# LM5161_Buck_Converter.net
KiCad netlist of a schematic drawn in Altium Designer
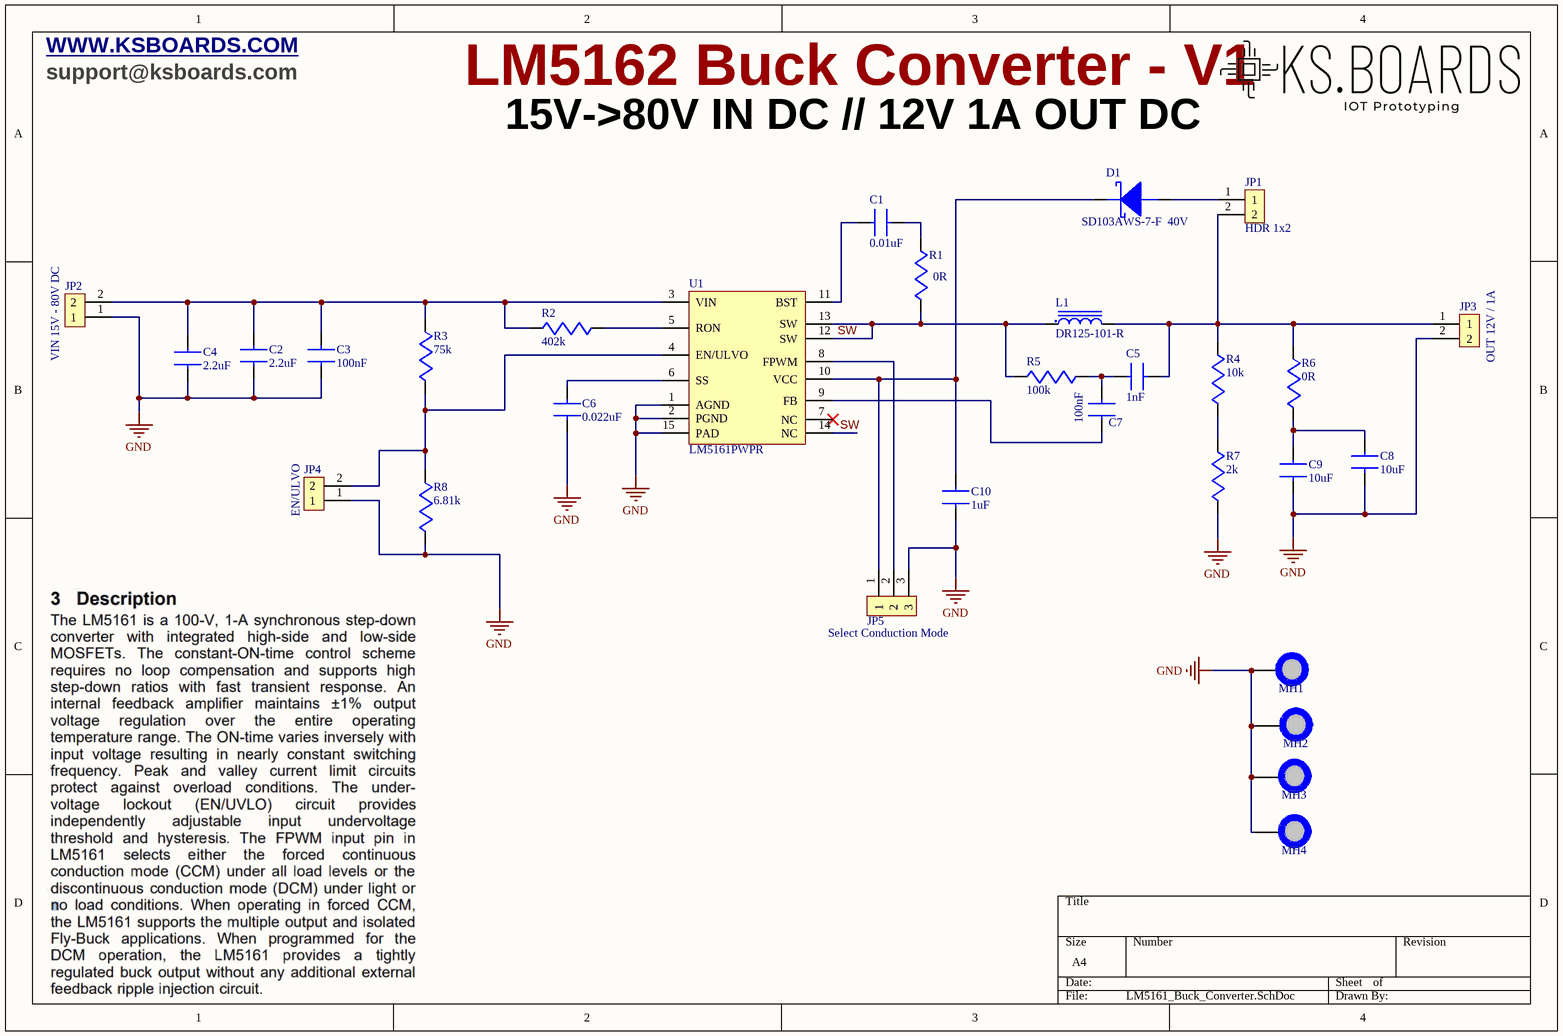
[diagram p0: LM5161_Buck_Converter.SchDoc]

(export (version "E")
  (design (tool "Eeschema 10.0.6"))
  (components
    (comp (ref "C1")
      (value "0.01uF")
      (footprint "C0603")
      (fields
        (field (name "MANUFACTURER") "KEMET")
        (field (name "MANUFACTURER PART NUMBER") "C0603X103K5RACTU")
        (field (name "TOLERANCE") "10%")
      )
      (libsource (lib "Buck_Conv_SCHLib") (part "C0603X103K5RACTU"))
    )
    (comp (ref "C2")
      (value "2.2uF")
      (footprint "C0603")
      (description "KEMET C0603C225K4PACTU - CAP, MLCC, X5R, 2.2UF, 16V, 0603")
      (fields
        (field (name "MANUFACTURER") "KEMET")
        (field (name "MANUFACTURER PART NUMBER") "C0603C225K4PACTU")
      )
      (libsource (lib "Buck_Conv_SCHLib") (part "C0603C225K4PACTU"))
    )
    (comp (ref "C3")
      (value "100nF")
      (footprint "C0603")
      (description "CAPACITOR CERAMIC, 0.1UF, 50V, X7R, 10%, 0603")
      (fields
        (field (name "MANUFACTURER") "Yageo")
        (field (name "MANUFACTURER PART NUMBER") "CC0603KRX7R9BB104")
      )
      (libsource (lib "Buck_Conv_SCHLib") (part "CC0603KRX7R9BB104"))
    )
    (comp (ref "C4")
      (value "2.2uF")
      (footprint "C0603")
      (description "KEMET C0603C225K4PACTU - CAP, MLCC, X5R, 2.2UF, 16V, 0603")
      (fields
        (field (name "MANUFACTURER") "KEMET")
        (field (name "MANUFACTURER PART NUMBER") "C0603C225K4PACTU")
      )
      (libsource (lib "Buck_Conv_SCHLib") (part "C0603C225K4PACTU"))
    )
    (comp (ref "C5")
      (value "1nF")
      (footprint "C0603")
      (fields
        (field (name "MANUFACTURER") "KEMET")
        (field (name "MANUFACTURER PART NUMBER") "C0603C102K5RACTU")
        (field (name "TOLERANCE") "10%")
      )
      (libsource (lib "Buck_Conv_SCHLib") (part "C0603C102K5RACTU"))
    )
    (comp (ref "C6")
      (value "0.022uF")
      (footprint "C0603")
      (description "Cap Ceramic 0.022uF 16V X7R 10% SMD 0603 125°C Paper T/R")
      (fields
        (field (name "MANUFACTURER") "KEMET")
        (field (name "MANUFACTURER PART NUMBER") "C0603C223K4RACTU")
      )
      (libsource (lib "Buck_Conv_SCHLib") (part "C0603C223K4RACTU"))
    )
    (comp (ref "C7")
      (value "100nF")
      (footprint "C0603")
      (description "CAPACITOR CERAMIC, 0.1UF, 50V, X7R, 10%, 0603")
      (fields
        (field (name "MANUFACTURER") "Yageo")
        (field (name "MANUFACTURER PART NUMBER") "CC0603KRX7R9BB104")
      )
      (libsource (lib "Buck_Conv_SCHLib") (part "CC0603KRX7R9BB104"))
    )
    (comp (ref "C8")
      (value "10uF")
      (footprint "C0603")
      (description "KEMET - C0603C106M9PACTU - CAP, MLCC, X5R, 10UF, 6.3V, 0603")
      (fields
        (field (name "MANUFACTURER") "KEMET")
        (field (name "MANUFACTURER PART NUMBER") "C0603C106M9PACTU")
      )
      (libsource (lib "Buck_Conv_SCHLib") (part "C0603C106M9PACTU"))
    )
    (comp (ref "C9")
      (value "10uF")
      (footprint "C0603")
      (description "KEMET - C0603C106M9PACTU - CAP, MLCC, X5R, 10UF, 6.3V, 0603")
      (fields
        (field (name "MANUFACTURER") "KEMET")
        (field (name "MANUFACTURER PART NUMBER") "C0603C106M9PACTU")
      )
      (libsource (lib "Buck_Conv_SCHLib") (part "C0603C106M9PACTU"))
    )
    (comp (ref "C10")
      (value "1uF")
      (footprint "C0603")
      (fields
        (field (name "MANUFACTURER") "KEMET")
        (field (name "MANUFACTURER PART NUMBER") "C0603C105K3PACTU")
        (field (name "TOLERANCE") "10%")
      )
      (libsource (lib "Buck_Conv_SCHLib") (part "C0603C105K3PACTU"))
    )
    (comp (ref "D1")
      (value "SD103AWS-7-F  40V")
      (footprint "SOD323")
      (description "Diode Schottky 40V 0.35A Automotive 2-Pin SOD-323 T/R")
      (fields (field (name "MANUFACTURER") "Diodes") (field (name "MANUFACTURER PART NUMBER") "SD103AWS-7-F"))
      (libsource (lib "Buck_Conv_SCHLib") (part "SD103AWS-7-F"))
    )
    (comp (ref "JP1")
      (value "HDR 1x2")
      (footprint "HDR_FEMALE_1x2_2.54mm")
      (description "TERMINAL BLOCK, WIRE TO BRD, 2POS, 16AWG")
      (fields
        (field (name "MANUFACTURER") "Phoenix Contact")
        (field (name "MANUFACTURER PART NUMBER") "1729128")
      )
      (libsource (lib "Buck_Conv_SCHLib") (part "1729128"))
    )
    (comp (ref "JP2")
      (value "VIN 15V - 80V DC")
      (footprint "HDR_FEMALE_1x2_2.54mm")
      (description "TERMINAL BLOCK, WIRE TO BRD, 2POS, 16AWG")
      (fields
        (field (name "MANUFACTURER") "Phoenix Contact")
        (field (name "MANUFACTURER PART NUMBER") "1729128")
      )
      (libsource (lib "") (part "1729128_1"))
    )
    (comp (ref "JP3")
      (value "OUT 12V / 1A")
      (footprint "HDR_FEMALE_1x2_2.54mm")
      (description "TERMINAL BLOCK, WIRE TO BRD, 2POS, 16AWG")
      (fields
        (field (name "MANUFACTURER") "Phoenix Contact")
        (field (name "MANUFACTURER PART NUMBER") "1729128")
      )
      (libsource (lib "Buck_Conv_SCHLib") (part "1729128"))
    )
    (comp (ref "JP4")
      (value "EN/ULVO")
      (footprint "HDR_FEMALE_1x2_2.54mm")
      (description "TERMINAL BLOCK, WIRE TO BRD, 2POS, 16AWG")
      (fields
        (field (name "MANUFACTURER") "Phoenix Contact")
        (field (name "MANUFACTURER PART NUMBER") "1729128")
      )
      (libsource (lib "") (part "1729128_1"))
    )
    (comp (ref "JP5")
      (value "Select Conduction Mode")
      (footprint "HDR_FEMALE_1x3_2.54mm")
      (description "MSTB 2 5/ 3-ST BD: 1-3")
      (fields
        (field (name "MANUFACTURER") "Phoenix Contact")
        (field (name "MANUFACTURER PART NUMBER") "1765344")
      )
      (libsource (lib "Buck_Conv_SCHLib") (part "1765344"))
    )
    (comp (ref "L1")
      (value "DR125-101-R")
      (footprint "IND2PADS")
      (description "Inductor Power Shielded Drum Core 102.7uH/100uH 20% 100KHz Ferrite 1.78A 170mOhm DCR T/R")
      (fields (field (name "MANUFACTURER") "Eaton Cooper") (field (name "TOLERANCE") "20%"))
      (libsource (lib "Buck_Conv_SCHLib") (part "DR125-101-R"))
    )
    (comp (ref "MH1")
      (value "MH_3.5MM_3.5MMD")
      (footprint "MH_3.5MMX3.5MM")
      (description "Mounting hole 3.5mm diameter 2mm drill hole")
      (libsource (lib "Buck_Conv_SCHLib") (part "MH_3.5MM_3.5MM"))
    )
    (comp (ref "MH2")
      (value "MH_3.5MM_3.5MMD")
      (footprint "MH_3.5MMX3.5MM")
      (description "Mounting hole 3.5mm diameter 2mm drill hole")
      (libsource (lib "Buck_Conv_SCHLib") (part "MH_3.5MM_3.5MM"))
    )
    (comp (ref "MH3")
      (value "MH_3.5MM_3.5MMD")
      (footprint "MH_3.5MMX3.5MM")
      (description "Mounting hole 3.5mm diameter 2mm drill hole")
      (libsource (lib "Buck_Conv_SCHLib") (part "MH_3.5MM_3.5MM"))
    )
    (comp (ref "MH4")
      (value "MH_3.5MM_3.5MMD")
      (footprint "MH_3.5MMX3.5MM")
      (description "Mounting hole 3.5mm diameter 2mm drill hole")
      (libsource (lib "Buck_Conv_SCHLib") (part "MH_3.5MM_3.5MM"))
    )
    (comp (ref "R1")
      (value "0R")
      (footprint "R0603")
      (description "VISHAY - CRCW06030000Z0EC - RES, AEC-Q200, THICK FILM, 0R, 0.1W, 0603")
      (fields
        (field (name "MANUFACTURER") "Vishay Dale")
        (field (name "MANUFACTURER PART NUMBER") "CRCW06030000Z0EC")
      )
      (libsource (lib "Buck_Conv_SCHLib") (part "CRCW06030000Z0EC"))
    )
    (comp (ref "R2")
      (value "402k")
      (footprint "R0603")
      (description "Res Thick Film 0603 402K Ohm 1% 0.1W(1/10W) ±100ppm/C Molded SMD Automotive Paper T/R")
      (fields
        (field (name "MANUFACTURER") "Vishay")
        (field (name "MANUFACTURER PART NUMBER") "CRCW0603402KFKEA")
      )
      (libsource (lib "Buck_Conv_SCHLib") (part "CRCW0603402KFKEA"))
    )
    (comp (ref "R3")
      (value "75k")
      (footprint "R0603")
      (description "Resistor;  Thick Film;  75 Kilohms;  0.1 W;  1%;  SMT;  0603;  TCR 37 ppm/DegC")
      (fields
        (field (name "MANUFACTURER") "Vishay")
        (field (name "MANUFACTURER PART NUMBER") "CRCW060375K0FKEA")
      )
      (libsource (lib "Buck_Conv_SCHLib") (part "CRCW060375K0FKEA"))
    )
    (comp (ref "R4")
      (value "10k")
      (footprint "R0603")
      (fields
        (field (name "MANUFACTURER") "Vishay")
        (field (name "MANUFACTURER PART NUMBER") "CRCW060310K0FKEA")
        (field (name "TOLERANCE") "1%")
      )
      (libsource (lib "Buck_Conv_SCHLib") (part "CRCW060310K0FKEA"))
    )
    (comp (ref "R5")
      (value "100k")
      (footprint "R0603")
      (description "Res Thick Film 1.6 x 0.8 mm 100K Ohm 1% 0.1W(1/10W) 100ppm/ C Molded SMD Paper T/R")
      (fields
        (field (name "MANUFACTURER") "Yageo")
        (field (name "MANUFACTURER PART NUMBER") "RC0603FR-07100KL")
      )
      (libsource (lib "Buck_Conv_SCHLib") (part "RC0603FR-07100KL"))
    )
    (comp (ref "R6")
      (value "0R")
      (footprint "R0603")
      (description "VISHAY - CRCW06030000Z0EC - RES, AEC-Q200, THICK FILM, 0R, 0.1W, 0603")
      (fields
        (field (name "MANUFACTURER") "Vishay Dale")
        (field (name "MANUFACTURER PART NUMBER") "CRCW06030000Z0EC")
      )
      (libsource (lib "Buck_Conv_SCHLib") (part "CRCW06030000Z0EC"))
    )
    (comp (ref "R7")
      (value "2k")
      (footprint "R0603")
      (description "D11/CRCW0603 100 2K 1% ET1 e3")
      (fields
        (field (name "MANUFACTURER") "Vishay")
        (field (name "MANUFACTURER PART NUMBER") "CRCW06032K00FKEA")
      )
      (libsource (lib "Buck_Conv_SCHLib") (part "CRCW06032K00FKEA"))
    )
    (comp (ref "R8")
      (value "6.81k")
      (footprint "R0603")
      (description "RES SMD 6.81K OHM 1% 1/10W 0603")
      (fields
        (field (name "MANUFACTURER") "Yageo")
        (field (name "MANUFACTURER PART NUMBER") "RC0603FR-076K81L")
      )
      (libsource (lib "Buck_Conv_SCHLib") (part "RC0603FR-076K81L"))
    )
    (comp (ref "U1")
      (value "LM5161PWPR")
      (footprint "SOP15")
      (description "IC REG BCK FLYBCK ISO 14HTSSOP")
      (fields (field (name "MANUFACTURER") "Texas Instruments"))
      (libsource (lib "Buck_Conv_SCHLib") (part "LM5161PWPR"))
    )
  )
  (nets
    (net (code "1") (name "/SW") (class "Default")
      (node (ref "L1") (pin "1") (pinfunction "1_1") (pintype "passive"))
      (node (ref "R1") (pin "1") (pinfunction "1_1") (pintype "passive"))
      (node (ref "R5") (pin "1") (pinfunction "1_1") (pintype "passive"))
      (node (ref "U1") (pin "12") (pinfunction "SW_12") (pintype "passive"))
      (node (ref "U1") (pin "13") (pinfunction "SW_13") (pintype "passive"))
      (node (ref "U1") (pin "14") (pinfunction "NC_14") (pintype "passive"))
    )
    (net (code "2") (name "GND") (class "Default")
      (node (ref "C10") (pin "1") (pinfunction "1_1") (pintype "passive"))
      (node (ref "C2") (pin "1") (pinfunction "1_1") (pintype "passive"))
      (node (ref "C3") (pin "1") (pinfunction "1_1") (pintype "passive"))
      (node (ref "C4") (pin "1") (pinfunction "1_1") (pintype "passive"))
      (node (ref "C6") (pin "1") (pinfunction "1_1") (pintype "passive"))
      (node (ref "C8") (pin "1") (pinfunction "1_1") (pintype "passive"))
      (node (ref "C9") (pin "1") (pinfunction "1_1") (pintype "passive"))
      (node (ref "JP2") (pin "1") (pinfunction "1_1") (pintype "passive"))
      (node (ref "JP3") (pin "2") (pinfunction "2_2") (pintype "passive"))
      (node (ref "JP4") (pin "1") (pinfunction "1_1") (pintype "passive"))
      (node (ref "JP5") (pin "3") (pinfunction "3_3") (pintype "passive"))
      (node (ref "MH1") (pin "1") (pinfunction "1_1") (pintype "passive"))
      (node (ref "MH2") (pin "1") (pinfunction "1_1") (pintype "passive"))
      (node (ref "MH3") (pin "1") (pinfunction "1_1") (pintype "passive"))
      (node (ref "MH4") (pin "1") (pinfunction "1_1") (pintype "passive"))
      (node (ref "R7") (pin "1") (pinfunction "1_1") (pintype "passive"))
      (node (ref "R8") (pin "1") (pinfunction "1_1") (pintype "passive"))
      (node (ref "U1") (pin "1") (pinfunction "AGND_1") (pintype "passive"))
      (node (ref "U1") (pin "15") (pinfunction "PAD_15") (pintype "passive"))
      (node (ref "U1") (pin "2") (pinfunction "PGND_2") (pintype "passive"))
    )
    (net (code "3") (name "Net-(C1-Pad2)") (class "Default")
      (node (ref "C1") (pin "2") (pinfunction "2_2") (pintype "passive"))
      (node (ref "R1") (pin "2") (pinfunction "2_2") (pintype "passive"))
    )
    (net (code "4") (name "Net-(C5-Pad1)") (class "Default")
      (node (ref "C5") (pin "1") (pinfunction "1_1") (pintype "passive"))
      (node (ref "JP1") (pin "2") (pinfunction "2_2") (pintype "passive"))
      (node (ref "JP3") (pin "1") (pinfunction "1_1") (pintype "passive"))
      (node (ref "L1") (pin "2") (pinfunction "2_2") (pintype "passive"))
      (node (ref "R4") (pin "2") (pinfunction "2_2") (pintype "passive"))
      (node (ref "R6") (pin "2") (pinfunction "2_2") (pintype "passive"))
    )
    (net (code "5") (name "Net-(C5-Pad2)") (class "Default")
      (node (ref "C5") (pin "2") (pinfunction "2_2") (pintype "passive"))
      (node (ref "C7") (pin "2") (pinfunction "2_2") (pintype "passive"))
      (node (ref "R5") (pin "2") (pinfunction "2_2") (pintype "passive"))
    )
    (net (code "6") (name "Net-(C8-Pad2)") (class "Default")
      (node (ref "C8") (pin "2") (pinfunction "2_2") (pintype "passive"))
      (node (ref "C9") (pin "2") (pinfunction "2_2") (pintype "passive"))
      (node (ref "R6") (pin "1") (pinfunction "1_1") (pintype "passive"))
    )
    (net (code "7") (name "Net-(D1-Anode)") (class "Default")
      (node (ref "D1") (pin "1") (pinfunction "Anode_1") (pintype "passive"))
      (node (ref "JP1") (pin "1") (pinfunction "1_1") (pintype "passive"))
    )
    (net (code "8") (name "Net-(D1-Cathode)") (class "Default")
      (node (ref "C10") (pin "2") (pinfunction "2_2") (pintype "passive"))
      (node (ref "D1") (pin "2") (pinfunction "Cathode_2") (pintype "passive"))
      (node (ref "JP5") (pin "1") (pinfunction "1_1") (pintype "passive"))
      (node (ref "U1") (pin "10") (pinfunction "VCC_10") (pintype "passive"))
    )
    (net (code "9") (name "Net-(R4-Pad1)") (class "Default")
      (node (ref "R4") (pin "1") (pinfunction "1_1") (pintype "passive"))
      (node (ref "R7") (pin "2") (pinfunction "2_2") (pintype "passive"))
    )
    (net (code "10") (name "Net-(U1-BST)") (class "Default")
      (node (ref "C1") (pin "1") (pinfunction "1_1") (pintype "passive"))
      (node (ref "U1") (pin "11") (pinfunction "BST_11") (pintype "passive"))
    )
    (net (code "11") (name "Net-(U1-EN{slash}ULVO)") (class "Default")
      (node (ref "JP4") (pin "2") (pinfunction "2_2") (pintype "passive"))
      (node (ref "R3") (pin "1") (pinfunction "1_1") (pintype "passive"))
      (node (ref "R8") (pin "2") (pinfunction "2_2") (pintype "passive"))
      (node (ref "U1") (pin "4") (pinfunction "EN/ULVO_4") (pintype "passive"))
    )
    (net (code "12") (name "Net-(U1-FB)") (class "Default")
      (node (ref "C7") (pin "1") (pinfunction "1_1") (pintype "passive"))
      (node (ref "U1") (pin "9") (pinfunction "FB_9") (pintype "passive"))
    )
    (net (code "13") (name "Net-(U1-FPWM)") (class "Default")
      (node (ref "JP5") (pin "2") (pinfunction "2_2") (pintype "passive"))
      (node (ref "U1") (pin "8") (pinfunction "FPWM_8") (pintype "passive"))
    )
    (net (code "14") (name "Net-(U1-RON)") (class "Default")
      (node (ref "R2") (pin "2") (pinfunction "2_2") (pintype "passive"))
      (node (ref "U1") (pin "5") (pinfunction "RON_5") (pintype "passive"))
    )
    (net (code "15") (name "Net-(U1-SS)") (class "Default")
      (node (ref "C6") (pin "2") (pinfunction "2_2") (pintype "passive"))
      (node (ref "U1") (pin "6") (pinfunction "SS_6") (pintype "passive"))
    )
    (net (code "16") (name "Net-(U1-VIN)") (class "Default")
      (node (ref "C2") (pin "2") (pinfunction "2_2") (pintype "passive"))
      (node (ref "C3") (pin "2") (pinfunction "2_2") (pintype "passive"))
      (node (ref "C4") (pin "2") (pinfunction "2_2") (pintype "passive"))
      (node (ref "JP2") (pin "2") (pinfunction "2_2") (pintype "passive"))
      (node (ref "R2") (pin "1") (pinfunction "1_1") (pintype "passive"))
      (node (ref "R3") (pin "2") (pinfunction "2_2") (pintype "passive"))
      (node (ref "U1") (pin "3") (pinfunction "VIN_3") (pintype "passive"))
    )
    (net (code "17") (name "unconnected-(U1-NC-Pad7)") (class "Default")
      (node (ref "U1") (pin "7") (pinfunction "NC_7") (pintype "passive+no_connect"))
    )
  )
)
